# cadiz_mb_20140314_5.net
KiCad netlist of a schematic drawn in EAGLE
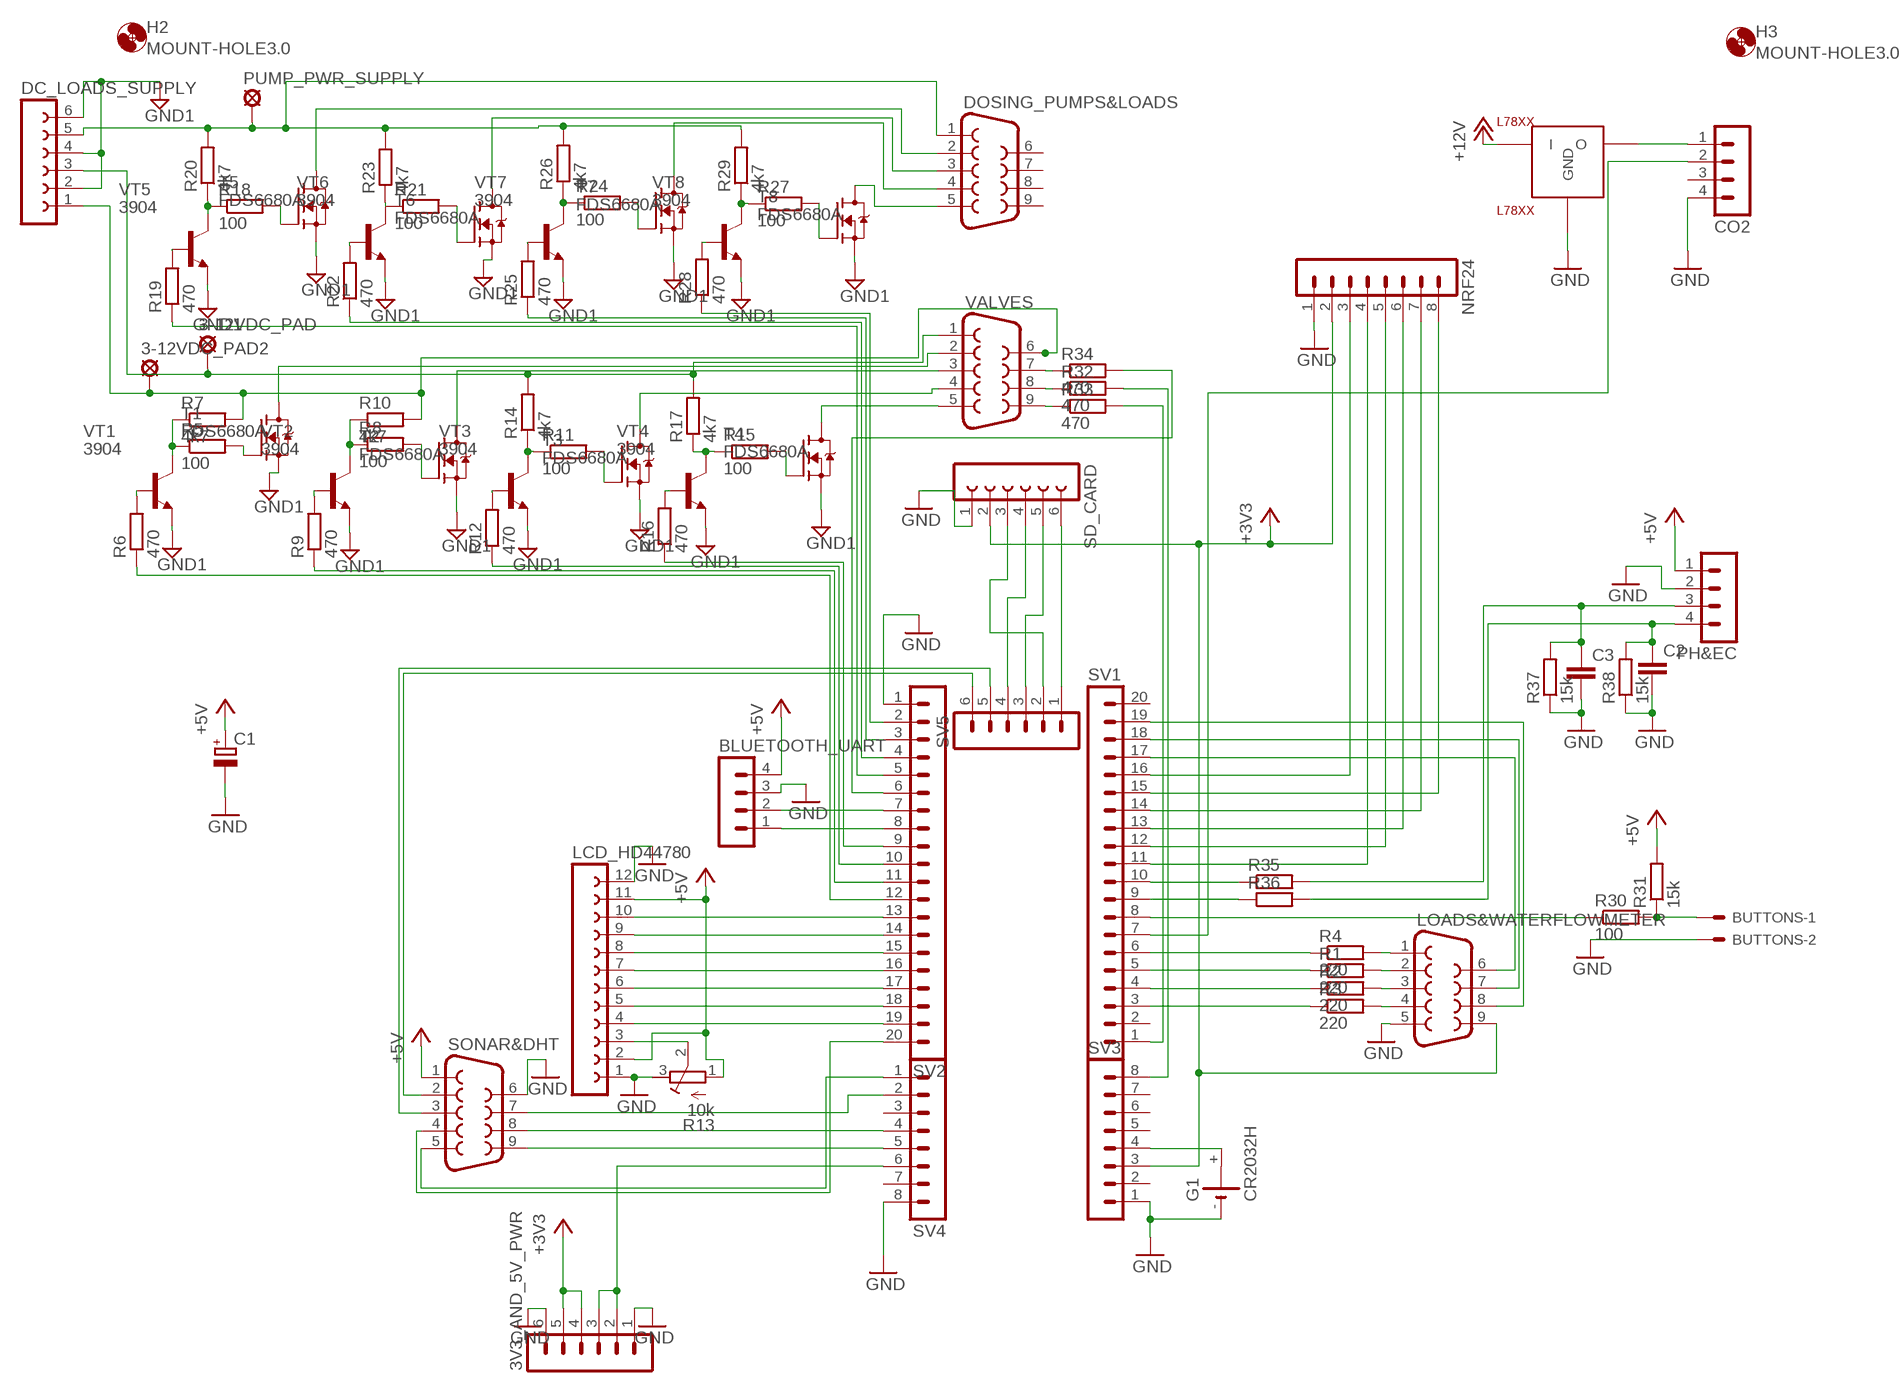
[diagram p0: schematic, sheet 1]

(export (version "E")
  (design (tool "Eeschema 10.0.6"))
  (components
    (comp (ref "3-12VDC_PAD")
      (value "LSP13")
      (footprint "eagle-import:LSP13")
      (libsource (lib "eagle-import") (part "LSP13"))
    )
    (comp (ref "3-12VDC_PAD2")
      (value "LSP13")
      (footprint "eagle-import:LSP13")
      (libsource (lib "eagle-import") (part "LSP13"))
    )
    (comp (ref "3V3_AND_5V_PWR")
      (value "MA06-1")
      (footprint "eagle-import:MA06-1")
      (libsource (lib "eagle-import") (part "MA06-1"))
    )
    (comp (ref "BLUETOOTH_UART")
      (value "MA04-1")
      (footprint "eagle-import:MA04-1")
      (libsource (lib "eagle-import") (part "MA04-1"))
    )
    (comp (ref "BUTTONS")
      (value "22-23-2021")
      (footprint "eagle-import:22-23-2021")
      (fields (field (name "MF") "MOLEX"))
      (libsource (lib "eagle-import") (part "22-23-2021"))
    )
    (comp (ref "C1")
      (value "CPOL-EUE5-13")
      (footprint "eagle-import:E5-13")
      (libsource (lib "eagle-import") (part "CPOL-EUE5-13"))
    )
    (comp (ref "C2")
      (value "C-EUC1206")
      (footprint "eagle-import:C1206")
      (libsource (lib "eagle-import") (part "C-EUC1206"))
    )
    (comp (ref "C3")
      (value "C-EUC1206")
      (footprint "eagle-import:C1206")
      (libsource (lib "eagle-import") (part "C-EUC1206"))
    )
    (comp (ref "CO2")
      (value "MA04-1")
      (footprint "eagle-import:MA04-1")
      (fields (field (name "OC_FARNELL") "unknown") (field (name "OC_NEWARK") "unknown"))
      (libsource (lib "eagle-import") (part "MA04-1"))
    )
    (comp (ref "DC_LOADS_SUPPLY")
      (value "FE06-1")
      (footprint "eagle-import:FE06")
      (libsource (lib "eagle-import") (part "FE06-1"))
    )
    (comp (ref "DOSING_PUMPS&LOADS")
      (value "F09HP")
      (footprint "eagle-import:F09HP")
      (libsource (lib "eagle-import") (part "F09HP"))
    )
    (comp (ref "G1")
      (value "CR2032H")
      (footprint "eagle-import:CR2032H")
      (libsource (lib "eagle-import") (part "CR2032H"))
    )
    (comp (ref "H2")
      (value "MOUNT-HOLE3.0")
      (footprint "eagle-import:3,0")
      (libsource (lib "eagle-import") (part "MOUNT-HOLE3.0"))
    )
    (comp (ref "H3")
      (value "MOUNT-HOLE3.0")
      (footprint "eagle-import:3,0")
      (libsource (lib "eagle-import") (part "MOUNT-HOLE3.0"))
    )
    (comp (ref "L7806")
      (value "L78XX")
      (footprint "eagle-import:TO220")
      (libsource (lib "eagle-import") (part "L78XX"))
    )
    (comp (ref "LCD_HD44780")
      (value "FE12-1")
      (footprint "eagle-import:FE12")
      (libsource (lib "eagle-import") (part "FE12-1"))
    )
    (comp (ref "LOADS&WATERFLOWMETER")
      (value "F09HP")
      (footprint "eagle-import:F09HP")
      (libsource (lib "eagle-import") (part "F09HP"))
    )
    (comp (ref "NRF24")
      (value "MA08-1")
      (footprint "eagle-import:MA08-1")
      (libsource (lib "eagle-import") (part "MA08-1"))
    )
    (comp (ref "PH&EC")
      (value "MA04-1")
      (footprint "eagle-import:MA04-1")
      (fields (field (name "OC_FARNELL") "unknown") (field (name "OC_NEWARK") "unknown"))
      (libsource (lib "eagle-import") (part "MA04-1"))
    )
    (comp (ref "PUMP_PWR_SUPPLY")
      (value "LSP13")
      (footprint "eagle-import:LSP13")
      (libsource (lib "eagle-import") (part "LSP13"))
    )
    (comp (ref "R1")
      (value "220")
      (footprint "eagle-import:M1206")
      (libsource (lib "eagle-import") (part "R-EU_M1206"))
    )
    (comp (ref "R2")
      (value "220")
      (footprint "eagle-import:M1206")
      (libsource (lib "eagle-import") (part "R-EU_M1206"))
    )
    (comp (ref "R3")
      (value "220")
      (footprint "eagle-import:M1206")
      (libsource (lib "eagle-import") (part "R-EU_M1206"))
    )
    (comp (ref "R4")
      (value "220")
      (footprint "eagle-import:M1206")
      (libsource (lib "eagle-import") (part "R-EU_M1206"))
    )
    (comp (ref "R5")
      (value "100")
      (footprint "eagle-import:M1206")
      (libsource (lib "eagle-import") (part "R-EU_M1206"))
    )
    (comp (ref "R6")
      (value "470")
      (footprint "eagle-import:M1206")
      (libsource (lib "eagle-import") (part "R-EU_M1206"))
    )
    (comp (ref "R7")
      (value "4k7")
      (footprint "eagle-import:M1206")
      (libsource (lib "eagle-import") (part "R-EU_M1206"))
    )
    (comp (ref "R8")
      (value "100")
      (footprint "eagle-import:M1206")
      (libsource (lib "eagle-import") (part "R-EU_M1206"))
    )
    (comp (ref "R9")
      (value "470")
      (footprint "eagle-import:M1206")
      (libsource (lib "eagle-import") (part "R-EU_M1206"))
    )
    (comp (ref "R10")
      (value "4k7")
      (footprint "eagle-import:M1206")
      (libsource (lib "eagle-import") (part "R-EU_M1206"))
    )
    (comp (ref "R11")
      (value "100")
      (footprint "eagle-import:M1206")
      (libsource (lib "eagle-import") (part "R-EU_M1206"))
    )
    (comp (ref "R12")
      (value "470")
      (footprint "eagle-import:M1206")
      (libsource (lib "eagle-import") (part "R-EU_M1206"))
    )
    (comp (ref "R13")
      (value "10k")
      (footprint "eagle-import:RTRIM3374")
      (libsource (lib "eagle-import") (part "R-TRIMM3374"))
    )
    (comp (ref "R14")
      (value "4k7")
      (footprint "eagle-import:M1206")
      (libsource (lib "eagle-import") (part "R-EU_M1206"))
    )
    (comp (ref "R15")
      (value "100")
      (footprint "eagle-import:M1206")
      (libsource (lib "eagle-import") (part "R-EU_M1206"))
    )
    (comp (ref "R16")
      (value "470")
      (footprint "eagle-import:M1206")
      (libsource (lib "eagle-import") (part "R-EU_M1206"))
    )
    (comp (ref "R17")
      (value "4k7")
      (footprint "eagle-import:M1206")
      (libsource (lib "eagle-import") (part "R-EU_M1206"))
    )
    (comp (ref "R18")
      (value "100")
      (footprint "eagle-import:M1206")
      (libsource (lib "eagle-import") (part "R-EU_M1206"))
    )
    (comp (ref "R19")
      (value "470")
      (footprint "eagle-import:M1206")
      (libsource (lib "eagle-import") (part "R-EU_M1206"))
    )
    (comp (ref "R20")
      (value "4k7")
      (footprint "eagle-import:M1206")
      (libsource (lib "eagle-import") (part "R-EU_M1206"))
    )
    (comp (ref "R21")
      (value "100")
      (footprint "eagle-import:M1206")
      (libsource (lib "eagle-import") (part "R-EU_M1206"))
    )
    (comp (ref "R22")
      (value "470")
      (footprint "eagle-import:M1206")
      (libsource (lib "eagle-import") (part "R-EU_M1206"))
    )
    (comp (ref "R23")
      (value "4k7")
      (footprint "eagle-import:M1206")
      (libsource (lib "eagle-import") (part "R-EU_M1206"))
    )
    (comp (ref "R24")
      (value "100")
      (footprint "eagle-import:M1206")
      (libsource (lib "eagle-import") (part "R-EU_M1206"))
    )
    (comp (ref "R25")
      (value "470")
      (footprint "eagle-import:M1206")
      (libsource (lib "eagle-import") (part "R-EU_M1206"))
    )
    (comp (ref "R26")
      (value "4k7")
      (footprint "eagle-import:M1206")
      (libsource (lib "eagle-import") (part "R-EU_M1206"))
    )
    (comp (ref "R27")
      (value "100")
      (footprint "eagle-import:M1206")
      (libsource (lib "eagle-import") (part "R-EU_M1206"))
    )
    (comp (ref "R28")
      (value "470")
      (footprint "eagle-import:M1206")
      (libsource (lib "eagle-import") (part "R-EU_M1206"))
    )
    (comp (ref "R29")
      (value "4k7")
      (footprint "eagle-import:M1206")
      (libsource (lib "eagle-import") (part "R-EU_M1206"))
    )
    (comp (ref "R30")
      (value "100")
      (footprint "eagle-import:M1206")
      (libsource (lib "eagle-import") (part "R-EU_M1206"))
    )
    (comp (ref "R31")
      (value "15k")
      (footprint "eagle-import:M1206")
      (libsource (lib "eagle-import") (part "R-EU_M1206"))
    )
    (comp (ref "R32")
      (value "470")
      (footprint "eagle-import:M1206")
      (libsource (lib "eagle-import") (part "R-EU_M1206"))
    )
    (comp (ref "R33")
      (value "470")
      (footprint "eagle-import:M1206")
      (libsource (lib "eagle-import") (part "R-EU_M1206"))
    )
    (comp (ref "R34")
      (value "470")
      (footprint "eagle-import:M1206")
      (libsource (lib "eagle-import") (part "R-EU_M1206"))
    )
    (comp (ref "R35")
      (value "R-EU_M1206")
      (footprint "eagle-import:M1206")
      (libsource (lib "eagle-import") (part "R-EU_M1206"))
    )
    (comp (ref "R36")
      (value "R-EU_M1206")
      (footprint "eagle-import:M1206")
      (libsource (lib "eagle-import") (part "R-EU_M1206"))
    )
    (comp (ref "R37")
      (value "15k")
      (footprint "eagle-import:M1206")
      (libsource (lib "eagle-import") (part "R-EU_M1206"))
    )
    (comp (ref "R38")
      (value "15k")
      (footprint "eagle-import:M1206")
      (libsource (lib "eagle-import") (part "R-EU_M1206"))
    )
    (comp (ref "SD_CARD")
      (value "FE06-1")
      (footprint "eagle-import:FE06")
      (libsource (lib "eagle-import") (part "FE06-1"))
    )
    (comp (ref "SONAR&DHT")
      (value "F09HP")
      (footprint "eagle-import:F09HP")
      (libsource (lib "eagle-import") (part "F09HP"))
    )
    (comp (ref "SV1")
      (value "MA20-1")
      (footprint "eagle-import:MA20-1")
      (libsource (lib "eagle-import") (part "MA20-1"))
    )
    (comp (ref "SV2")
      (value "MA20-1")
      (footprint "eagle-import:MA20-1")
      (libsource (lib "eagle-import") (part "MA20-1"))
    )
    (comp (ref "SV3")
      (value "MA08-1")
      (footprint "eagle-import:MA08-1")
      (libsource (lib "eagle-import") (part "MA08-1"))
    )
    (comp (ref "SV4")
      (value "MA08-1")
      (footprint "eagle-import:MA08-1")
      (libsource (lib "eagle-import") (part "MA08-1"))
    )
    (comp (ref "SV5")
      (value "MA06-1")
      (footprint "eagle-import:MA06-1")
      (libsource (lib "eagle-import") (part "MA06-1"))
    )
    (comp (ref "T1")
      (value "FDS6680A")
      (footprint "eagle-import:SO8")
      (libsource (lib "eagle-import") (part "FDS6680A_SOP8"))
    )
    (comp (ref "T2")
      (value "FDS6680A")
      (footprint "eagle-import:SO8")
      (libsource (lib "eagle-import") (part "FDS6680A_SOP8"))
    )
    (comp (ref "T3")
      (value "FDS6680A")
      (footprint "eagle-import:SO8")
      (libsource (lib "eagle-import") (part "FDS6680A_SOP8"))
    )
    (comp (ref "T4")
      (value "FDS6680A")
      (footprint "eagle-import:SO8")
      (libsource (lib "eagle-import") (part "FDS6680A_SOP8"))
    )
    (comp (ref "T5")
      (value "FDS6680A")
      (footprint "eagle-import:SO8")
      (libsource (lib "eagle-import") (part "FDS6680A_SOP8"))
    )
    (comp (ref "T6")
      (value "FDS6680A")
      (footprint "eagle-import:SO8")
      (libsource (lib "eagle-import") (part "FDS6680A_SOP8"))
    )
    (comp (ref "T7")
      (value "FDS6680A")
      (footprint "eagle-import:SO8")
      (libsource (lib "eagle-import") (part "FDS6680A_SOP8"))
    )
    (comp (ref "T8")
      (value "FDS6680A")
      (footprint "eagle-import:SO8")
      (libsource (lib "eagle-import") (part "FDS6680A_SOP8"))
    )
    (comp (ref "VALVES")
      (value "F09HP")
      (footprint "eagle-import:F09HP")
      (libsource (lib "eagle-import") (part "F09HP"))
    )
    (comp (ref "VT1")
      (value "3904")
      (footprint "eagle-import:SOT23")
      (libsource (lib "eagle-import") (part "BC847"))
    )
    (comp (ref "VT2")
      (value "3904")
      (footprint "eagle-import:SOT23")
      (libsource (lib "eagle-import") (part "BC847"))
    )
    (comp (ref "VT3")
      (value "3904")
      (footprint "eagle-import:SOT23")
      (libsource (lib "eagle-import") (part "BC847"))
    )
    (comp (ref "VT4")
      (value "3904")
      (footprint "eagle-import:SOT23")
      (libsource (lib "eagle-import") (part "BC847"))
    )
    (comp (ref "VT5")
      (value "3904")
      (footprint "eagle-import:SOT23")
      (libsource (lib "eagle-import") (part "BC847"))
    )
    (comp (ref "VT6")
      (value "3904")
      (footprint "eagle-import:SOT23")
      (libsource (lib "eagle-import") (part "BC847"))
    )
    (comp (ref "VT7")
      (value "3904")
      (footprint "eagle-import:SOT23")
      (libsource (lib "eagle-import") (part "BC847"))
    )
    (comp (ref "VT8")
      (value "3904")
      (footprint "eagle-import:SOT23")
      (libsource (lib "eagle-import") (part "BC847"))
    )
  )
  (nets
    (net (code "1") (name "+3V3") (class "Default")
      (node (ref "3V3_AND_5V_PWR") (pin "4") (pinfunction "4_4") (pintype "passive"))
      (node (ref "3V3_AND_5V_PWR") (pin "5") (pinfunction "5_5") (pintype "passive"))
      (node (ref "LOADS&WATERFLOWMETER") (pin "9") (pinfunction "9_9") (pintype "passive"))
      (node (ref "NRF24") (pin "2") (pinfunction "2_2") (pintype "passive"))
      (node (ref "SD_CARD") (pin "2") (pinfunction "2_2") (pintype "passive"))
      (node (ref "SV3") (pin "3") (pinfunction "3_3") (pintype "passive"))
    )
    (net (code "2") (name "+5V") (class "Default")
      (node (ref "BLUETOOTH_UART") (pin "4") (pinfunction "4_4") (pintype "passive"))
      (node (ref "C1") (pin "+") (pinfunction "+_+") (pintype "passive"))
      (node (ref "LCD_HD44780") (pin "11") (pinfunction "11_11") (pintype "passive"))
      (node (ref "LCD_HD44780") (pin "2") (pinfunction "2_2") (pintype "passive"))
      (node (ref "PH&EC") (pin "1") (pinfunction "1_1") (pintype "passive"))
      (node (ref "R13") (pin "1") (pinfunction "E_1") (pintype "passive"))
      (node (ref "R31") (pin "2") (pinfunction "2_2") (pintype "passive"))
      (node (ref "SONAR&DHT") (pin "1") (pinfunction "1_1") (pintype "passive"))
    )
    (net (code "3") (name "+12V") (class "Default")
      (node (ref "L7806") (pin "IN") (pinfunction "I_IN") (pintype "power_in"))
    )
    (net (code "4") (name "GND") (class "Default")
      (node (ref "3V3_AND_5V_PWR") (pin "1") (pinfunction "1_1") (pintype "passive"))
      (node (ref "3V3_AND_5V_PWR") (pin "6") (pinfunction "6_6") (pintype "passive"))
      (node (ref "BLUETOOTH_UART") (pin "3") (pinfunction "3_3") (pintype "passive"))
      (node (ref "BUTTONS") (pin "2") (pinfunction "S_2") (pintype "passive"))
      (node (ref "C1") (pin "-") (pinfunction "-_-") (pintype "passive"))
      (node (ref "C2") (pin "2") (pinfunction "2_2") (pintype "passive"))
      (node (ref "C3") (pin "2") (pinfunction "2_2") (pintype "passive"))
      (node (ref "CO2") (pin "4") (pinfunction "4_4") (pintype "passive"))
      (node (ref "G1") (pin "-") (pinfunction "-_-") (pintype "passive"))
      (node (ref "L7806") (pin "GND") (pinfunction "GND_GND") (pintype "power_in"))
      (node (ref "LCD_HD44780") (pin "1") (pinfunction "1_1") (pintype "passive"))
      (node (ref "LCD_HD44780") (pin "12") (pinfunction "12_12") (pintype "passive"))
      (node (ref "LOADS&WATERFLOWMETER") (pin "5") (pinfunction "5_5") (pintype "passive"))
      (node (ref "NRF24") (pin "1") (pinfunction "1_1") (pintype "passive"))
      (node (ref "PH&EC") (pin "2") (pinfunction "2_2") (pintype "passive"))
      (node (ref "R13") (pin "3") (pinfunction "A_3") (pintype "passive"))
      (node (ref "R37") (pin "1") (pinfunction "1_1") (pintype "passive"))
      (node (ref "R38") (pin "1") (pinfunction "1_1") (pintype "passive"))
      (node (ref "SD_CARD") (pin "1") (pinfunction "1_1") (pintype "passive"))
      (node (ref "SONAR&DHT") (pin "6") (pinfunction "6_6") (pintype "passive"))
      (node (ref "SV2") (pin "1") (pinfunction "1_1") (pintype "passive"))
      (node (ref "SV3") (pin "1") (pinfunction "1_1") (pintype "passive"))
      (node (ref "SV4") (pin "8") (pinfunction "8_8") (pintype "passive"))
    )
    (net (code "5") (name "GND1") (class "Default")
      (node (ref "DC_LOADS_SUPPLY") (pin "2") (pinfunction "2_2") (pintype "passive"))
      (node (ref "DC_LOADS_SUPPLY") (pin "4") (pinfunction "4_4") (pintype "passive"))
      (node (ref "DC_LOADS_SUPPLY") (pin "6") (pinfunction "6_6") (pintype "passive"))
      (node (ref "T1") (pin "SOURCE") (pinfunction "S_SOURCE") (pintype "passive"))
      (node (ref "T2") (pin "SOURCE") (pinfunction "S_SOURCE") (pintype "passive"))
      (node (ref "T3") (pin "SOURCE") (pinfunction "S_SOURCE") (pintype "passive"))
      (node (ref "T4") (pin "SOURCE") (pinfunction "S_SOURCE") (pintype "passive"))
      (node (ref "T5") (pin "SOURCE") (pinfunction "S_SOURCE") (pintype "passive"))
      (node (ref "T6") (pin "SOURCE") (pinfunction "S_SOURCE") (pintype "passive"))
      (node (ref "T7") (pin "SOURCE") (pinfunction "S_SOURCE") (pintype "passive"))
      (node (ref "T8") (pin "SOURCE") (pinfunction "S_SOURCE") (pintype "passive"))
      (node (ref "VT1") (pin "2") (pinfunction "E_2") (pintype "passive"))
      (node (ref "VT2") (pin "2") (pinfunction "E_2") (pintype "passive"))
      (node (ref "VT3") (pin "2") (pinfunction "E_2") (pintype "passive"))
      (node (ref "VT4") (pin "2") (pinfunction "E_2") (pintype "passive"))
      (node (ref "VT5") (pin "2") (pinfunction "E_2") (pintype "passive"))
      (node (ref "VT6") (pin "2") (pinfunction "E_2") (pintype "passive"))
      (node (ref "VT7") (pin "2") (pinfunction "E_2") (pintype "passive"))
      (node (ref "VT8") (pin "2") (pinfunction "E_2") (pintype "passive"))
    )
    (net (code "6") (name "Net-(3-12VDC_PAD-PadMP)") (class "Default")
      (node (ref "3-12VDC_PAD") (pin "MP") (pinfunction "MP_MP") (pintype "passive"))
      (node (ref "DC_LOADS_SUPPLY") (pin "3") (pinfunction "3_3") (pintype "passive"))
      (node (ref "R14") (pin "2") (pinfunction "2_2") (pintype "passive"))
      (node (ref "R17") (pin "2") (pinfunction "2_2") (pintype "passive"))
      (node (ref "VALVES") (pin "1") (pinfunction "1_1") (pintype "passive"))
    )
    (net (code "7") (name "Net-(3-12VDC_PAD2-PadMP)") (class "Default")
      (node (ref "3-12VDC_PAD2") (pin "MP") (pinfunction "MP_MP") (pintype "passive"))
      (node (ref "DC_LOADS_SUPPLY") (pin "1") (pinfunction "1_1") (pintype "passive"))
      (node (ref "R10") (pin "2") (pinfunction "2_2") (pintype "passive"))
      (node (ref "R7") (pin "2") (pinfunction "2_2") (pintype "passive"))
      (node (ref "VALVES") (pin "6") (pinfunction "6_6") (pintype "passive"))
    )
    (net (code "8") (name "Net-(3V3_AND_5V_PWR-Pad2)") (class "Default")
      (node (ref "3V3_AND_5V_PWR") (pin "2") (pinfunction "2_2") (pintype "passive"))
      (node (ref "3V3_AND_5V_PWR") (pin "3") (pinfunction "3_3") (pintype "passive"))
      (node (ref "SV4") (pin "6") (pinfunction "6_6") (pintype "passive"))
    )
    (net (code "9") (name "Net-(BLUETOOTH_UART-Pad1)") (class "Default")
      (node (ref "BLUETOOTH_UART") (pin "1") (pinfunction "1_1") (pintype "passive"))
      (node (ref "SV2") (pin "8") (pinfunction "8_8") (pintype "passive"))
    )
    (net (code "10") (name "Net-(BLUETOOTH_UART-Pad2)") (class "Default")
      (node (ref "BLUETOOTH_UART") (pin "2") (pinfunction "2_2") (pintype "passive"))
      (node (ref "SV2") (pin "7") (pinfunction "7_7") (pintype "passive"))
    )
    (net (code "11") (name "Net-(BUTTONSA-S)") (class "Default")
      (node (ref "BUTTONS") (pin "1") (pinfunction "S_1") (pintype "passive"))
      (node (ref "R30") (pin "2") (pinfunction "2_2") (pintype "passive"))
      (node (ref "R31") (pin "1") (pinfunction "1_1") (pintype "passive"))
    )
    (net (code "12") (name "Net-(C2-Pad1)") (class "Default")
      (node (ref "C2") (pin "1") (pinfunction "1_1") (pintype "passive"))
      (node (ref "PH&EC") (pin "4") (pinfunction "4_4") (pintype "passive"))
      (node (ref "R36") (pin "2") (pinfunction "2_2") (pintype "passive"))
      (node (ref "R38") (pin "2") (pinfunction "2_2") (pintype "passive"))
    )
    (net (code "13") (name "Net-(C3-Pad1)") (class "Default")
      (node (ref "C3") (pin "1") (pinfunction "1_1") (pintype "passive"))
      (node (ref "PH&EC") (pin "3") (pinfunction "3_3") (pintype "passive"))
      (node (ref "R35") (pin "2") (pinfunction "2_2") (pintype "passive"))
      (node (ref "R37") (pin "2") (pinfunction "2_2") (pintype "passive"))
    )
    (net (code "14") (name "Net-(CO2-Pad2)") (class "Default")
      (node (ref "CO2") (pin "2") (pinfunction "2_2") (pintype "passive"))
      (node (ref "SV1") (pin "7") (pinfunction "7_7") (pintype "passive"))
    )
    (net (code "15") (name "Net-(DC_LOADS_SUPPLY-Pad5)") (class "Default")
      (node (ref "DC_LOADS_SUPPLY") (pin "5") (pinfunction "5_5") (pintype "passive"))
      (node (ref "DOSING_PUMPS&LOADS") (pin "1") (pinfunction "1_1") (pintype "passive"))
      (node (ref "PUMP_PWR_SUPPLY") (pin "MP") (pinfunction "MP_MP") (pintype "passive"))
      (node (ref "R20") (pin "2") (pinfunction "2_2") (pintype "passive"))
      (node (ref "R23") (pin "2") (pinfunction "2_2") (pintype "passive"))
      (node (ref "R26") (pin "2") (pinfunction "2_2") (pintype "passive"))
      (node (ref "R29") (pin "2") (pinfunction "2_2") (pintype "passive"))
    )
    (net (code "16") (name "Net-(G1-Pad+)") (class "Default")
      (node (ref "G1") (pin "+") (pinfunction "+_+") (pintype "passive"))
      (node (ref "SV3") (pin "4") (pinfunction "4_4") (pintype "passive"))
    )
    (net (code "17") (name "Net-(L7806-O)") (class "Default")
      (node (ref "CO2") (pin "1") (pinfunction "1_1") (pintype "passive"))
      (node (ref "L7806") (pin "OUT") (pinfunction "O_OUT") (pintype "power_in"))
    )
    (net (code "18") (name "Net-(LCD_HD44780-Pad4)") (class "Default")
      (node (ref "LCD_HD44780") (pin "4") (pinfunction "4_4") (pintype "passive"))
      (node (ref "SV2") (pin "19") (pinfunction "19_19") (pintype "passive"))
    )
    (net (code "19") (name "Net-(LCD_HD44780-Pad5)") (class "Default")
      (node (ref "LCD_HD44780") (pin "5") (pinfunction "5_5") (pintype "passive"))
      (node (ref "SV2") (pin "18") (pinfunction "18_18") (pintype "passive"))
    )
    (net (code "20") (name "Net-(LCD_HD44780-Pad6)") (class "Default")
      (node (ref "LCD_HD44780") (pin "6") (pinfunction "6_6") (pintype "passive"))
      (node (ref "SV2") (pin "17") (pinfunction "17_17") (pintype "passive"))
    )
    (net (code "21") (name "Net-(LCD_HD44780-Pad7)") (class "Default")
      (node (ref "LCD_HD44780") (pin "7") (pinfunction "7_7") (pintype "passive"))
      (node (ref "SV2") (pin "16") (pinfunction "16_16") (pintype "passive"))
    )
    (net (code "22") (name "Net-(LCD_HD44780-Pad8)") (class "Default")
      (node (ref "LCD_HD44780") (pin "8") (pinfunction "8_8") (pintype "passive"))
      (node (ref "SV2") (pin "15") (pinfunction "15_15") (pintype "passive"))
    )
    (net (code "23") (name "Net-(LCD_HD44780-Pad9)") (class "Default")
      (node (ref "LCD_HD44780") (pin "9") (pinfunction "9_9") (pintype "passive"))
      (node (ref "SV2") (pin "14") (pinfunction "14_14") (pintype "passive"))
    )
    (net (code "24") (name "Net-(LCD_HD44780-Pad10)") (class "Default")
      (node (ref "LCD_HD44780") (pin "10") (pinfunction "10_10") (pintype "passive"))
      (node (ref "SV2") (pin "13") (pinfunction "13_13") (pintype "passive"))
    )
    (net (code "25") (name "Net-(LOADS&WATERFLOWMETER-Pad1)") (class "Default")
      (node (ref "LOADS&WATERFLOWMETER") (pin "1") (pinfunction "1_1") (pintype "passive"))
      (node (ref "R4") (pin "2") (pinfunction "2_2") (pintype "passive"))
    )
    (net (code "26") (name "Net-(LOADS&WATERFLOWMETER-Pad2)") (class "Default")
      (node (ref "LOADS&WATERFLOWMETER") (pin "2") (pinfunction "2_2") (pintype "passive"))
      (node (ref "R1") (pin "2") (pinfunction "2_2") (pintype "passive"))
    )
    (net (code "27") (name "Net-(LOADS&WATERFLOWMETER-Pad3)") (class "Default")
      (node (ref "LOADS&WATERFLOWMETER") (pin "3") (pinfunction "3_3") (pintype "passive"))
      (node (ref "R2") (pin "2") (pinfunction "2_2") (pintype "passive"))
    )
    (net (code "28") (name "Net-(LOADS&WATERFLOWMETER-Pad4)") (class "Default")
      (node (ref "LOADS&WATERFLOWMETER") (pin "4") (pinfunction "4_4") (pintype "passive"))
      (node (ref "R3") (pin "2") (pinfunction "2_2") (pintype "passive"))
    )
    (net (code "29") (name "Net-(LOADS&WATERFLOWMETER-Pad6)") (class "Default")
      (node (ref "LOADS&WATERFLOWMETER") (pin "6") (pinfunction "6_6") (pintype "passive"))
      (node (ref "SV1") (pin "17") (pinfunction "17_17") (pintype "passive"))
    )
    (net (code "30") (name "Net-(LOADS&WATERFLOWMETER-Pad7)") (class "Default")
      (node (ref "LOADS&WATERFLOWMETER") (pin "7") (pinfunction "7_7") (pintype "passive"))
      (node (ref "SV1") (pin "18") (pinfunction "18_18") (pintype "passive"))
    )
    (net (code "31") (name "Net-(LOADS&WATERFLOWMETER-Pad8)") (class "Default")
      (node (ref "LOADS&WATERFLOWMETER") (pin "8") (pinfunction "8_8") (pintype "passive"))
      (node (ref "SV1") (pin "19") (pinfunction "19_19") (pintype "passive"))
    )
    (net (code "32") (name "Net-(NRF24-Pad3)") (class "Default")
      (node (ref "NRF24") (pin "3") (pinfunction "3_3") (pintype "passive"))
      (node (ref "SV1") (pin "16") (pinfunction "16_16") (pintype "passive"))
    )
    (net (code "33") (name "Net-(NRF24-Pad4)") (class "Default")
      (node (ref "NRF24") (pin "4") (pinfunction "4_4") (pintype "passive"))
      (node (ref "SV1") (pin "11") (pinfunction "11_11") (pintype "passive"))
    )
    (net (code "34") (name "Net-(NRF24-Pad5)") (class "Default")
      (node (ref "NRF24") (pin "5") (pinfunction "5_5") (pintype "passive"))
      (node (ref "SV1") (pin "12") (pinfunction "12_12") (pintype "passive"))
    )
    (net (code "35") (name "Net-(NRF24-Pad6)") (class "Default")
      (node (ref "NRF24") (pin "6") (pinfunction "6_6") (pintype "passive"))
      (node (ref "SV1") (pin "13") (pinfunction "13_13") (pintype "passive"))
    )
    (net (code "36") (name "Net-(NRF24-Pad7)") (class "Default")
      (node (ref "NRF24") (pin "7") (pinfunction "7_7") (pintype "passive"))
      (node (ref "SV1") (pin "14") (pinfunction "14_14") (pintype "passive"))
    )
    (net (code "37") (name "Net-(NRF24-Pad8)") (class "Default")
      (node (ref "NRF24") (pin "8") (pinfunction "8_8") (pintype "passive"))
      (node (ref "SV1") (pin "15") (pinfunction "15_15") (pintype "passive"))
    )
    (net (code "38") (name "Net-(R1-Pad1)") (class "Default")
      (node (ref "R1") (pin "1") (pinfunction "1_1") (pintype "passive"))
      (node (ref "SV1") (pin "5") (pinfunction "5_5") (pintype "passive"))
    )
    (net (code "39") (name "Net-(R2-Pad1)") (class "Default")
      (node (ref "R2") (pin "1") (pinfunction "1_1") (pintype "passive"))
      (node (ref "SV1") (pin "4") (pinfunction "4_4") (pintype "passive"))
    )
    (net (code "40") (name "Net-(R3-Pad1)") (class "Default")
      (node (ref "R3") (pin "1") (pinfunction "1_1") (pintype "passive"))
      (node (ref "SV1") (pin "3") (pinfunction "3_3") (pintype "passive"))
    )
    (net (code "41") (name "Net-(R4-Pad1)") (class "Default")
      (node (ref "R4") (pin "1") (pinfunction "1_1") (pintype "passive"))
      (node (ref "SV1") (pin "6") (pinfunction "6_6") (pintype "passive"))
    )
    (net (code "42") (name "Net-(R6-Pad1)") (class "Default")
      (node (ref "R6") (pin "1") (pinfunction "1_1") (pintype "passive"))
      (node (ref "SV2") (pin "12") (pinfunction "12_12") (pintype "passive"))
    )
    (net (code "43") (name "Net-(R9-Pad1)") (class "Default")
      (node (ref "R9") (pin "1") (pinfunction "1_1") (pintype "passive"))
      (node (ref "SV2") (pin "11") (pinfunction "11_11") (pintype "passive"))
    )
    (net (code "44") (name "Net-(R12-Pad1)") (class "Default")
      (node (ref "R12") (pin "1") (pinfunction "1_1") (pintype "passive"))
      (node (ref "SV2") (pin "10") (pinfunction "10_10") (pintype "passive"))
    )
    (net (code "45") (name "Net-(R13-S)") (class "Default")
      (node (ref "LCD_HD44780") (pin "3") (pinfunction "3_3") (pintype "passive"))
      (node (ref "R13") (pin "2") (pinfunction "S_2") (pintype "passive"))
    )
    (net (code "46") (name "Net-(R16-Pad1)") (class "Default")
      (node (ref "R16") (pin "1") (pinfunction "1_1") (pintype "passive"))
      (node (ref "SV2") (pin "9") (pinfunction "9_9") (pintype "passive"))
    )
    (net (code "47") (name "Net-(R19-Pad1)") (class "Default")
      (node (ref "R19") (pin "1") (pinfunction "1_1") (pintype "passive"))
      (node (ref "SV2") (pin "5") (pinfunction "5_5") (pintype "passive"))
    )
    (net (code "48") (name "Net-(R22-Pad1)") (class "Default")
      (node (ref "R22") (pin "1") (pinfunction "1_1") (pintype "passive"))
      (node (ref "SV2") (pin "4") (pinfunction "4_4") (pintype "passive"))
    )
    (net (code "49") (name "Net-(R25-Pad1)") (class "Default")
      (node (ref "R25") (pin "1") (pinfunction "1_1") (pintype "passive"))
      (node (ref "SV2") (pin "3") (pinfunction "3_3") (pintype "passive"))
    )
    (net (code "50") (name "Net-(R28-Pad1)") (class "Default")
      (node (ref "R28") (pin "1") (pinfunction "1_1") (pintype "passive"))
      (node (ref "SV2") (pin "2") (pinfunction "2_2") (pintype "passive"))
    )
    (net (code "51") (name "Net-(R30-Pad1)") (class "Default")
      (node (ref "R30") (pin "1") (pinfunction "1_1") (pintype "passive"))
      (node (ref "SV1") (pin "8") (pinfunction "8_8") (pintype "passive"))
    )
    (net (code "52") (name "Net-(R32-Pad1)") (class "Default")
      (node (ref "R32") (pin "1") (pinfunction "1_1") (pintype "passive"))
      (node (ref "VALVES") (pin "8") (pinfunction "8_8") (pintype "passive"))
    )
    (net (code "53") (name "Net-(R32-Pad2)") (class "Default")
      (node (ref "R32") (pin "2") (pinfunction "2_2") (pintype "passive"))
      (node (ref "SV3") (pin "8") (pinfunction "8_8") (pintype "passive"))
    )
    (net (code "54") (name "Net-(R33-Pad1)") (class "Default")
      (node (ref "R33") (pin "1") (pinfunction "1_1") (pintype "passive"))
      (node (ref "VALVES") (pin "9") (pinfunction "9_9") (pintype "passive"))
    )
    (net (code "55") (name "Net-(R33-Pad2)") (class "Default")
      (node (ref "R33") (pin "2") (pinfunction "2_2") (pintype "passive"))
      (node (ref "SV1") (pin "1") (pinfunction "1_1") (pintype "passive"))
    )
    (net (code "56") (name "Net-(R34-Pad1)") (class "Default")
      (node (ref "R34") (pin "1") (pinfunction "1_1") (pintype "passive"))
      (node (ref "VALVES") (pin "7") (pinfunction "7_7") (pintype "passive"))
    )
    (net (code "57") (name "Net-(R34-Pad2)") (class "Default")
      (node (ref "R34") (pin "2") (pinfunction "2_2") (pintype "passive"))
      (node (ref "SV2") (pin "6") (pinfunction "6_6") (pintype "passive"))
    )
    (net (code "58") (name "Net-(R35-Pad1)") (class "Default")
      (node (ref "R35") (pin "1") (pinfunction "1_1") (pintype "passive"))
      (node (ref "SV1") (pin "10") (pinfunction "10_10") (pintype "passive"))
    )
    (net (code "59") (name "Net-(R36-Pad1)") (class "Default")
      (node (ref "R36") (pin "1") (pinfunction "1_1") (pintype "passive"))
      (node (ref "SV1") (pin "9") (pinfunction "9_9") (pintype "passive"))
    )
    (net (code "60") (name "Net-(SD_CARD-Pad3)") (class "Default")
      (node (ref "SD_CARD") (pin "3") (pinfunction "3_3") (pintype "passive"))
      (node (ref "SV5") (pin "2") (pinfunction "2_2") (pintype "passive"))
    )
    (net (code "61") (name "Net-(SD_CARD-Pad4)") (class "Default")
      (node (ref "SD_CARD") (pin "4") (pinfunction "4_4") (pintype "passive"))
      (node (ref "SV5") (pin "4") (pinfunction "4_4") (pintype "passive"))
    )
    (net (code "62") (name "Net-(SD_CARD-Pad5)") (class "Default")
      (node (ref "SD_CARD") (pin "5") (pinfunction "5_5") (pintype "passive"))
      (node (ref "SV5") (pin "3") (pinfunction "3_3") (pintype "passive"))
    )
    (net (code "63") (name "Net-(SD_CARD-Pad6)") (class "Default")
      (node (ref "SD_CARD") (pin "6") (pinfunction "6_6") (pintype "passive"))
      (node (ref "SV5") (pin "1") (pinfunction "1_1") (pintype "passive"))
    )
    (net (code "64") (name "Net-(SONAR&DHT-Pad2)") (class "Default")
      (node (ref "SONAR&DHT") (pin "2") (pinfunction "2_2") (pintype "passive"))
      (node (ref "SV5") (pin "6") (pinfunction "6_6") (pintype "passive"))
    )
    (net (code "65") (name "Net-(SONAR&DHT-Pad3)") (class "Default")
      (node (ref "SONAR&DHT") (pin "3") (pinfunction "3_3") (pintype "passive"))
      (node (ref "SV5") (pin "5") (pinfunction "5_5") (pintype "passive"))
    )
    (net (code "66") (name "Net-(SONAR&DHT-Pad4)") (class "Default")
      (node (ref "SONAR&DHT") (pin "4") (pinfunction "4_4") (pintype "passive"))
      (node (ref "SV2") (pin "20") (pinfunction "20_20") (pintype "passive"))
    )
    (net (code "67") (name "Net-(SONAR&DHT-Pad5)") (class "Default")
      (node (ref "SONAR&DHT") (pin "5") (pinfunction "5_5") (pintype "passive"))
      (node (ref "SV4") (pin "1") (pinfunction "1_1") (pintype "passive"))
    )
    (net (code "68") (name "Net-(SONAR&DHT-Pad7)") (class "Default")
      (node (ref "SONAR&DHT") (pin "7") (pinfunction "7_7") (pintype "passive"))
      (node (ref "SV4") (pin "2") (pinfunction "2_2") (pintype "passive"))
    )
    (net (code "69") (name "Net-(SONAR&DHT-Pad8)") (class "Default")
      (node (ref "SONAR&DHT") (pin "8") (pinfunction "8_8") (pintype "passive"))
      (node (ref "SV4") (pin "4") (pinfunction "4_4") (pintype "passive"))
    )
    (net (code "70") (name "Net-(SONAR&DHT-Pad9)") (class "Default")
      (node (ref "SONAR&DHT") (pin "9") (pinfunction "9_9") (pintype "passive"))
      (node (ref "SV4") (pin "5") (pinfunction "5_5") (pintype "passive"))
    )
    (net (code "71") (name "Net-(T1-D)") (class "Default")
      (node (ref "T1") (pin "DRAIN") (pinfunction "D_DRAIN") (pintype "passive"))
      (node (ref "VALVES") (pin "2") (pinfunction "2_2") (pintype "passive"))
    )
    (net (code "72") (name "Net-(T1-G)") (class "Default")
      (node (ref "R5") (pin "2") (pinfunction "2_2") (pintype "passive"))
      (node (ref "T1") (pin "GATE") (pinfunction "G_GATE") (pintype "passive"))
    )
    (net (code "73") (name "Net-(T2-D)") (class "Default")
      (node (ref "T2") (pin "DRAIN") (pinfunction "D_DRAIN") (pintype "passive"))
      (node (ref "VALVES") (pin "3") (pinfunction "3_3") (pintype "passive"))
    )
    (net (code "74") (name "Net-(T2-G)") (class "Default")
      (node (ref "R8") (pin "2") (pinfunction "2_2") (pintype "passive"))
      (node (ref "T2") (pin "GATE") (pinfunction "G_GATE") (pintype "passive"))
    )
    (net (code "75") (name "Net-(T3-D)") (class "Default")
      (node (ref "T3") (pin "DRAIN") (pinfunction "D_DRAIN") (pintype "passive"))
      (node (ref "VALVES") (pin "4") (pinfunction "4_4") (pintype "passive"))
    )
    (net (code "76") (name "Net-(T3-G)") (class "Default")
      (node (ref "R11") (pin "2") (pinfunction "2_2") (pintype "passive"))
      (node (ref "T3") (pin "GATE") (pinfunction "G_GATE") (pintype "passive"))
    )
    (net (code "77") (name "Net-(T4-D)") (class "Default")
      (node (ref "T4") (pin "DRAIN") (pinfunction "D_DRAIN") (pintype "passive"))
      (node (ref "VALVES") (pin "5") (pinfunction "5_5") (pintype "passive"))
    )
    (net (code "78") (name "Net-(T4-G)") (class "Default")
      (node (ref "R15") (pin "2") (pinfunction "2_2") (pintype "passive"))
      (node (ref "T4") (pin "GATE") (pinfunction "G_GATE") (pintype "passive"))
    )
    (net (code "79") (name "Net-(T5-D)") (class "Default")
      (node (ref "DOSING_PUMPS&LOADS") (pin "2") (pinfunction "2_2") (pintype "passive"))
      (node (ref "T5") (pin "DRAIN") (pinfunction "D_DRAIN") (pintype "passive"))
    )
    (net (code "80") (name "Net-(T5-G)") (class "Default")
      (node (ref "R18") (pin "2") (pinfunction "2_2") (pintype "passive"))
      (node (ref "T5") (pin "GATE") (pinfunction "G_GATE") (pintype "passive"))
    )
    (net (code "81") (name "Net-(T6-D)") (class "Default")
      (node (ref "DOSING_PUMPS&LOADS") (pin "3") (pinfunction "3_3") (pintype "passive"))
      (node (ref "T6") (pin "DRAIN") (pinfunction "D_DRAIN") (pintype "passive"))
    )
    (net (code "82") (name "Net-(T6-G)") (class "Default")
      (node (ref "R21") (pin "2") (pinfunction "2_2") (pintype "passive"))
      (node (ref "T6") (pin "GATE") (pinfunction "G_GATE") (pintype "passive"))
    )
    (net (code "83") (name "Net-(T7-D)") (class "Default")
      (node (ref "DOSING_PUMPS&LOADS") (pin "4") (pinfunction "4_4") (pintype "passive"))
      (node (ref "T7") (pin "DRAIN") (pinfunction "D_DRAIN") (pintype "passive"))
    )
    (net (code "84") (name "Net-(T7-G)") (class "Default")
      (node (ref "R24") (pin "2") (pinfunction "2_2") (pintype "passive"))
      (node (ref "T7") (pin "GATE") (pinfunction "G_GATE") (pintype "passive"))
    )
    (net (code "85") (name "Net-(T8-D)") (class "Default")
      (node (ref "DOSING_PUMPS&LOADS") (pin "5") (pinfunction "5_5") (pintype "passive"))
      (node (ref "T8") (pin "DRAIN") (pinfunction "D_DRAIN") (pintype "passive"))
    )
    (net (code "86") (name "Net-(T8-G)") (class "Default")
      (node (ref "R27") (pin "2") (pinfunction "2_2") (pintype "passive"))
      (node (ref "T8") (pin "GATE") (pinfunction "G_GATE") (pintype "passive"))
    )
    (net (code "87") (name "Net-(VT1-B)") (class "Default")
      (node (ref "R6") (pin "2") (pinfunction "2_2") (pintype "passive"))
      (node (ref "VT1") (pin "1") (pinfunction "B_1") (pintype "passive"))
    )
    (net (code "88") (name "Net-(VT1-C)") (class "Default")
      (node (ref "R5") (pin "1") (pinfunction "1_1") (pintype "passive"))
      (node (ref "R7") (pin "1") (pinfunction "1_1") (pintype "passive"))
      (node (ref "VT1") (pin "3") (pinfunction "C_3") (pintype "passive"))
    )
    (net (code "89") (name "Net-(VT2-B)") (class "Default")
      (node (ref "R9") (pin "2") (pinfunction "2_2") (pintype "passive"))
      (node (ref "VT2") (pin "1") (pinfunction "B_1") (pintype "passive"))
    )
    (net (code "90") (name "Net-(VT2-C)") (class "Default")
      (node (ref "R10") (pin "1") (pinfunction "1_1") (pintype "passive"))
      (node (ref "R8") (pin "1") (pinfunction "1_1") (pintype "passive"))
      (node (ref "VT2") (pin "3") (pinfunction "C_3") (pintype "passive"))
    )
    (net (code "91") (name "Net-(VT3-B)") (class "Default")
      (node (ref "R12") (pin "2") (pinfunction "2_2") (pintype "passive"))
      (node (ref "VT3") (pin "1") (pinfunction "B_1") (pintype "passive"))
    )
    (net (code "92") (name "Net-(VT3-C)") (class "Default")
      (node (ref "R11") (pin "1") (pinfunction "1_1") (pintype "passive"))
      (node (ref "R14") (pin "1") (pinfunction "1_1") (pintype "passive"))
      (node (ref "VT3") (pin "3") (pinfunction "C_3") (pintype "passive"))
    )
    (net (code "93") (name "Net-(VT4-B)") (class "Default")
      (node (ref "R16") (pin "2") (pinfunction "2_2") (pintype "passive"))
      (node (ref "VT4") (pin "1") (pinfunction "B_1") (pintype "passive"))
    )
    (net (code "94") (name "Net-(VT4-C)") (class "Default")
      (node (ref "R15") (pin "1") (pinfunction "1_1") (pintype "passive"))
      (node (ref "R17") (pin "1") (pinfunction "1_1") (pintype "passive"))
      (node (ref "VT4") (pin "3") (pinfunction "C_3") (pintype "passive"))
    )
    (net (code "95") (name "Net-(VT5-B)") (class "Default")
      (node (ref "R19") (pin "2") (pinfunction "2_2") (pintype "passive"))
      (node (ref "VT5") (pin "1") (pinfunction "B_1") (pintype "passive"))
    )
    (net (code "96") (name "Net-(VT5-C)") (class "Default")
      (node (ref "R18") (pin "1") (pinfunction "1_1") (pintype "passive"))
      (node (ref "R20") (pin "1") (pinfunction "1_1") (pintype "passive"))
      (node (ref "VT5") (pin "3") (pinfunction "C_3") (pintype "passive"))
    )
    (net (code "97") (name "Net-(VT6-B)") (class "Default")
      (node (ref "R22") (pin "2") (pinfunction "2_2") (pintype "passive"))
      (node (ref "VT6") (pin "1") (pinfunction "B_1") (pintype "passive"))
    )
    (net (code "98") (name "Net-(VT6-C)") (class "Default")
      (node (ref "R21") (pin "1") (pinfunction "1_1") (pintype "passive"))
      (node (ref "R23") (pin "1") (pinfunction "1_1") (pintype "passive"))
      (node (ref "VT6") (pin "3") (pinfunction "C_3") (pintype "passive"))
    )
    (net (code "99") (name "Net-(VT7-B)") (class "Default")
      (node (ref "R25") (pin "2") (pinfunction "2_2") (pintype "passive"))
      (node (ref "VT7") (pin "1") (pinfunction "B_1") (pintype "passive"))
    )
    (net (code "100") (name "Net-(VT7-C)") (class "Default")
      (node (ref "R24") (pin "1") (pinfunction "1_1") (pintype "passive"))
      (node (ref "R26") (pin "1") (pinfunction "1_1") (pintype "passive"))
      (node (ref "VT7") (pin "3") (pinfunction "C_3") (pintype "passive"))
    )
    (net (code "101") (name "Net-(VT8-B)") (class "Default")
      (node (ref "R28") (pin "2") (pinfunction "2_2") (pintype "passive"))
      (node (ref "VT8") (pin "1") (pinfunction "B_1") (pintype "passive"))
    )
    (net (code "102") (name "Net-(VT8-C)") (class "Default")
      (node (ref "R27") (pin "1") (pinfunction "1_1") (pintype "passive"))
      (node (ref "R29") (pin "1") (pinfunction "1_1") (pintype "passive"))
      (node (ref "VT8") (pin "3") (pinfunction "C_3") (pintype "passive"))
    )
    (net (code "103") (name "unconnected-(CO2-Pad3)") (class "Default")
      (node (ref "CO2") (pin "3") (pinfunction "3_3") (pintype "passive"))
    )
    (net (code "104") (name "unconnected-(DOSING_PUMPS&LOADS-Pad6)") (class "Default")
      (node (ref "DOSING_PUMPS&LOADS") (pin "6") (pinfunction "6_6") (pintype "passive"))
    )
    (net (code "105") (name "unconnected-(DOSING_PUMPS&LOADS-Pad7)") (class "Default")
      (node (ref "DOSING_PUMPS&LOADS") (pin "7") (pinfunction "7_7") (pintype "passive"))
    )
    (net (code "106") (name "unconnected-(DOSING_PUMPS&LOADS-Pad8)") (class "Default")
      (node (ref "DOSING_PUMPS&LOADS") (pin "8") (pinfunction "8_8") (pintype "passive"))
    )
    (net (code "107") (name "unconnected-(DOSING_PUMPS&LOADS-Pad9)") (class "Default")
      (node (ref "DOSING_PUMPS&LOADS") (pin "9") (pinfunction "9_9") (pintype "passive"))
    )
    (net (code "108") (name "unconnected-(G1-+-Pad+@1)") (class "Default")
      (node (ref "G1") (pin "+@1") (pinfunction "+_+@1") (pintype "passive"))
    )
    (net (code "109") (name "unconnected-(SV1-Pad2)") (class "Default")
      (node (ref "SV1") (pin "2") (pinfunction "2_2") (pintype "passive"))
    )
    (net (code "110") (name "unconnected-(SV1-Pad20)") (class "Default")
      (node (ref "SV1") (pin "20") (pinfunction "20_20") (pintype "passive"))
    )
    (net (code "111") (name "unconnected-(SV3-Pad2)") (class "Default")
      (node (ref "SV3") (pin "2") (pinfunction "2_2") (pintype "passive"))
    )
    (net (code "112") (name "unconnected-(SV3-Pad5)") (class "Default")
      (node (ref "SV3") (pin "5") (pinfunction "5_5") (pintype "passive"))
    )
    (net (code "113") (name "unconnected-(SV3-Pad6)") (class "Default")
      (node (ref "SV3") (pin "6") (pinfunction "6_6") (pintype "passive"))
    )
    (net (code "114") (name "unconnected-(SV3-Pad7)") (class "Default")
      (node (ref "SV3") (pin "7") (pinfunction "7_7") (pintype "passive"))
    )
    (net (code "115") (name "unconnected-(SV4-Pad3)") (class "Default")
      (node (ref "SV4") (pin "3") (pinfunction "3_3") (pintype "passive"))
    )
    (net (code "116") (name "unconnected-(SV4-Pad7)") (class "Default")
      (node (ref "SV4") (pin "7") (pinfunction "7_7") (pintype "passive"))
    )
  )
)
